# babymidimultiplexgnusbuino.net
KiCad netlist of a schematic drawn in EAGLE
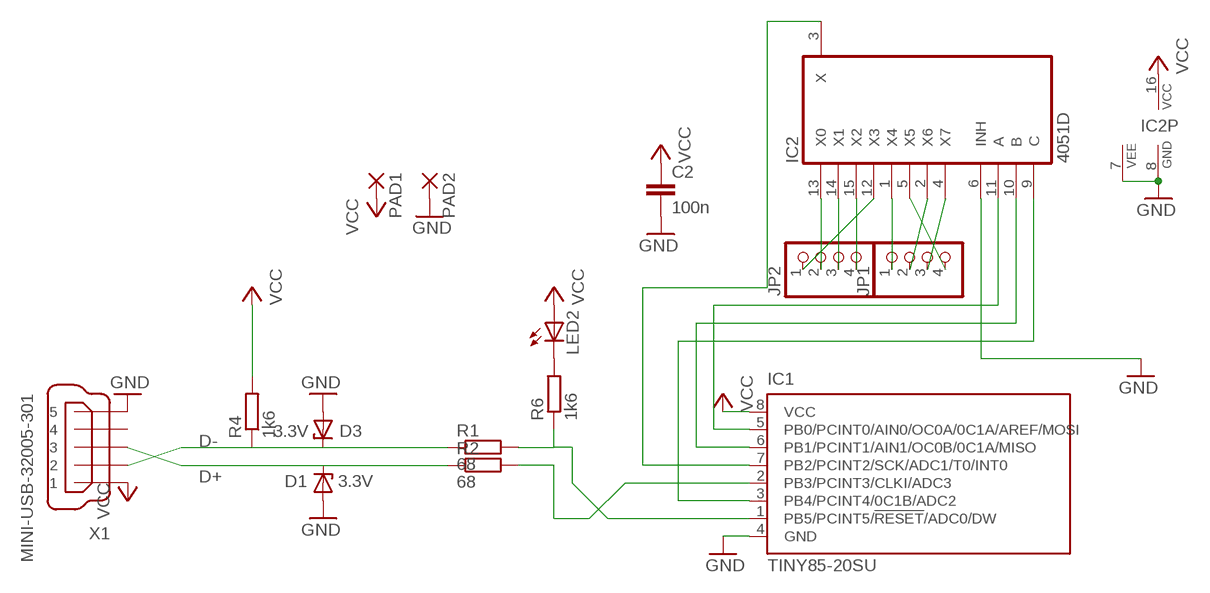
[diagram p0: schematic, sheet 1]

(export (version "E")
  (design (tool "Eeschema 10.0.6"))
  (components
    (comp (ref "C2")
      (value "100n")
      (footprint "eagle-import:C0603")
      (libsource (lib "eagle-import") (part "C-EUC0603"))
    )
    (comp (ref "D1")
      (value "3.3V")
      (footprint "eagle-import:SOD80C")
      (libsource (lib "eagle-import") (part "ZENER-DIODESOD80C"))
    )
    (comp (ref "D3")
      (value "3.3V")
      (footprint "eagle-import:SOD80C")
      (libsource (lib "eagle-import") (part "ZENER-DIODESOD80C"))
    )
    (comp (ref "IC1")
      (value "TINY85-20SU")
      (footprint "eagle-import:8S2")
      (fields
        (field (name "MPN") "ATTINY13-20SU")
        (field (name "MPN_1") "ATTINY13-20SU")
        (field (name "OC_FARNELL") "9171568")
        (field (name "OC_NEWARK") "96K6522")
      )
      (libsource (lib "eagle-import") (part "TINY85SU-20"))
    )
    (comp (ref "IC2")
      (value "4051D")
      (footprint "eagle-import:SO16")
      (libsource (lib "eagle-import") (part "4051D"))
    )
    (comp (ref "JP1")
      (value "PINHD-1X4")
      (footprint "eagle-import:1X04")
      (libsource (lib "eagle-import") (part "PINHD-1X4"))
    )
    (comp (ref "JP2")
      (value "PINHD-1X4")
      (footprint "eagle-import:1X04")
      (libsource (lib "eagle-import") (part "PINHD-1X4"))
    )
    (comp (ref "LED2")
      (value "LEDKA-3528ASYC")
      (footprint "eagle-import:KA-3528ASYC")
      (libsource (lib "eagle-import") (part "LEDKA-3528ASYC"))
    )
    (comp (ref "PAD1")
      (value "SMD5")
      (footprint "eagle-import:SMD2,54-5,08")
      (libsource (lib "eagle-import") (part "SMD5"))
    )
    (comp (ref "PAD2")
      (value "SMD5")
      (footprint "eagle-import:SMD2,54-5,08")
      (libsource (lib "eagle-import") (part "SMD5"))
    )
    (comp (ref "R1")
      (value "68")
      (footprint "eagle-import:R1206")
      (libsource (lib "eagle-import") (part "R-EU_R1206"))
    )
    (comp (ref "R2")
      (value "68")
      (footprint "eagle-import:R1206")
      (libsource (lib "eagle-import") (part "R-EU_R1206"))
    )
    (comp (ref "R4")
      (value "1k6")
      (footprint "eagle-import:R1206")
      (libsource (lib "eagle-import") (part "R-EU_R1206"))
    )
    (comp (ref "R6")
      (value "1k6")
      (footprint "eagle-import:R1206")
      (libsource (lib "eagle-import") (part "R-EU_R1206"))
    )
    (comp (ref "X1")
      (value "MINI-USB-32005-301")
      (footprint "eagle-import:32005-301")
      (libsource (lib "eagle-import") (part "MINI-USB-32005-301"))
    )
  )
  (nets
    (net (code "1") (name "/D+") (class "Default")
      (node (ref "D1") (pin "C") (pinfunction "C_C") (pintype "passive"))
      (node (ref "R2") (pin "1") (pinfunction "1_1") (pintype "passive"))
      (node (ref "X1") (pin "3") (pinfunction "3_3") (pintype "passive"))
    )
    (net (code "2") (name "/D-") (class "Default")
      (node (ref "D3") (pin "C") (pinfunction "C_C") (pintype "passive"))
      (node (ref "R1") (pin "1") (pinfunction "1_1") (pintype "passive"))
      (node (ref "R4") (pin "1") (pinfunction "1_1") (pintype "passive"))
      (node (ref "X1") (pin "2") (pinfunction "2_2") (pintype "passive"))
    )
    (net (code "3") (name "GND") (class "Default")
      (node (ref "C2") (pin "2") (pinfunction "2_2") (pintype "passive"))
      (node (ref "D1") (pin "A") (pinfunction "A_A") (pintype "passive"))
      (node (ref "D3") (pin "A") (pinfunction "A_A") (pintype "passive"))
      (node (ref "IC1") (pin "4") (pinfunction "GND_4") (pintype "power_in"))
      (node (ref "IC2") (pin "6") (pinfunction "INH_6") (pintype "input"))
      (node (ref "IC2") (pin "7") (pinfunction "VEE_7") (pintype "power_in"))
      (node (ref "IC2") (pin "8") (pinfunction "GND_8") (pintype "power_in"))
      (node (ref "PAD2") (pin "1") (pinfunction "P_1") (pintype "passive"))
      (node (ref "X1") (pin "5") (pinfunction "5_5") (pintype "passive"))
    )
    (net (code "4") (name "Net-(IC1-PB0{slash}PCINT0{slash}AIN0{slash}OC0A{slash}0C1A{slash}AREF{slash}MOSI)") (class "Default")
      (node (ref "IC1") (pin "5") (pinfunction "PB0/PCINT0/AIN0/OC0A/0C1A/AREF/MOSI_5") (pintype "bidirectional"))
      (node (ref "IC2") (pin "11") (pinfunction "A_11") (pintype "input"))
    )
    (net (code "5") (name "Net-(IC1-PB1{slash}PCINT1{slash}AIN1{slash}OC0B{slash}0C1A{slash}MISO)") (class "Default")
      (node (ref "IC1") (pin "6") (pinfunction "PB1/PCINT1/AIN1/OC0B/0C1A/MISO_6") (pintype "bidirectional"))
      (node (ref "IC2") (pin "10") (pinfunction "B_10") (pintype "input"))
    )
    (net (code "6") (name "Net-(IC1-PB2{slash}PCINT2{slash}SCK{slash}ADC1{slash}T0{slash}INT0)") (class "Default")
      (node (ref "IC1") (pin "7") (pinfunction "PB2/PCINT2/SCK/ADC1/T0/INT0_7") (pintype "bidirectional"))
      (node (ref "IC2") (pin "3") (pinfunction "X_3") (pintype "bidirectional"))
    )
    (net (code "7") (name "Net-(IC1-PB3{slash}PCINT3{slash}CLKI{slash}ADC3)") (class "Default")
      (node (ref "IC1") (pin "2") (pinfunction "PB3/PCINT3/CLKI/ADC3_2") (pintype "bidirectional"))
      (node (ref "R2") (pin "2") (pinfunction "2_2") (pintype "passive"))
    )
    (net (code "8") (name "Net-(IC1-PB4{slash}PCINT4{slash}0C1B{slash}ADC2)") (class "Default")
      (node (ref "IC1") (pin "3") (pinfunction "PB4/PCINT4/0C1B/ADC2_3") (pintype "bidirectional"))
      (node (ref "IC2") (pin "9") (pinfunction "C_9") (pintype "input"))
    )
    (net (code "9") (name "Net-(IC1-PB5{slash}PCINT5{slash}~{RESET}{slash}ADC0{slash}DW)") (class "Default")
      (node (ref "IC1") (pin "1") (pinfunction "PB5/PCINT5/~{RESET}/ADC0/DW_1") (pintype "bidirectional"))
      (node (ref "R1") (pin "2") (pinfunction "2_2") (pintype "passive"))
      (node (ref "R6") (pin "1") (pinfunction "1_1") (pintype "passive"))
    )
    (net (code "10") (name "Net-(IC2A-X0)") (class "Default")
      (node (ref "IC2") (pin "13") (pinfunction "X0_13") (pintype "bidirectional"))
      (node (ref "JP2") (pin "2") (pinfunction "2_2") (pintype "passive"))
    )
    (net (code "11") (name "Net-(IC2A-X1)") (class "Default")
      (node (ref "IC2") (pin "14") (pinfunction "X1_14") (pintype "bidirectional"))
      (node (ref "JP2") (pin "3") (pinfunction "3_3") (pintype "passive"))
    )
    (net (code "12") (name "Net-(IC2A-X2)") (class "Default")
      (node (ref "IC2") (pin "15") (pinfunction "X2_15") (pintype "bidirectional"))
      (node (ref "JP2") (pin "4") (pinfunction "4_4") (pintype "passive"))
    )
    (net (code "13") (name "Net-(IC2A-X3)") (class "Default")
      (node (ref "IC2") (pin "12") (pinfunction "X3_12") (pintype "bidirectional"))
      (node (ref "JP2") (pin "1") (pinfunction "1_1") (pintype "passive"))
    )
    (net (code "14") (name "Net-(IC2A-X4)") (class "Default")
      (node (ref "IC2") (pin "1") (pinfunction "X4_1") (pintype "bidirectional"))
      (node (ref "JP1") (pin "1") (pinfunction "1_1") (pintype "passive"))
    )
    (net (code "15") (name "Net-(IC2A-X5)") (class "Default")
      (node (ref "IC2") (pin "5") (pinfunction "X5_5") (pintype "bidirectional"))
      (node (ref "JP1") (pin "4") (pinfunction "4_4") (pintype "passive"))
    )
    (net (code "16") (name "Net-(IC2A-X6)") (class "Default")
      (node (ref "IC2") (pin "2") (pinfunction "X6_2") (pintype "bidirectional"))
      (node (ref "JP1") (pin "2") (pinfunction "2_2") (pintype "passive"))
    )
    (net (code "17") (name "Net-(IC2A-X7)") (class "Default")
      (node (ref "IC2") (pin "4") (pinfunction "X7_4") (pintype "bidirectional"))
      (node (ref "JP1") (pin "3") (pinfunction "3_3") (pintype "passive"))
    )
    (net (code "18") (name "Net-(LED2-PadC)") (class "Default")
      (node (ref "LED2") (pin "C") (pinfunction "C_C") (pintype "passive"))
      (node (ref "R6") (pin "2") (pinfunction "2_2") (pintype "passive"))
    )
    (net (code "19") (name "VCC") (class "Default")
      (node (ref "C2") (pin "1") (pinfunction "1_1") (pintype "passive"))
      (node (ref "IC1") (pin "8") (pinfunction "VCC_8") (pintype "power_in"))
      (node (ref "IC2") (pin "16") (pinfunction "VCC_16") (pintype "power_in"))
      (node (ref "LED2") (pin "A") (pinfunction "A_A") (pintype "passive"))
      (node (ref "PAD1") (pin "1") (pinfunction "P_1") (pintype "passive"))
      (node (ref "R4") (pin "2") (pinfunction "2_2") (pintype "passive"))
      (node (ref "X1") (pin "1") (pinfunction "1_1") (pintype "passive"))
    )
    (net (code "20") (name "unconnected-(X1-Pad4)") (class "Default")
      (node (ref "X1") (pin "4") (pinfunction "4_4") (pintype "passive"))
    )
  )
)
